# Schematic.net
KiCad netlist of a schematic drawn in EAGLE
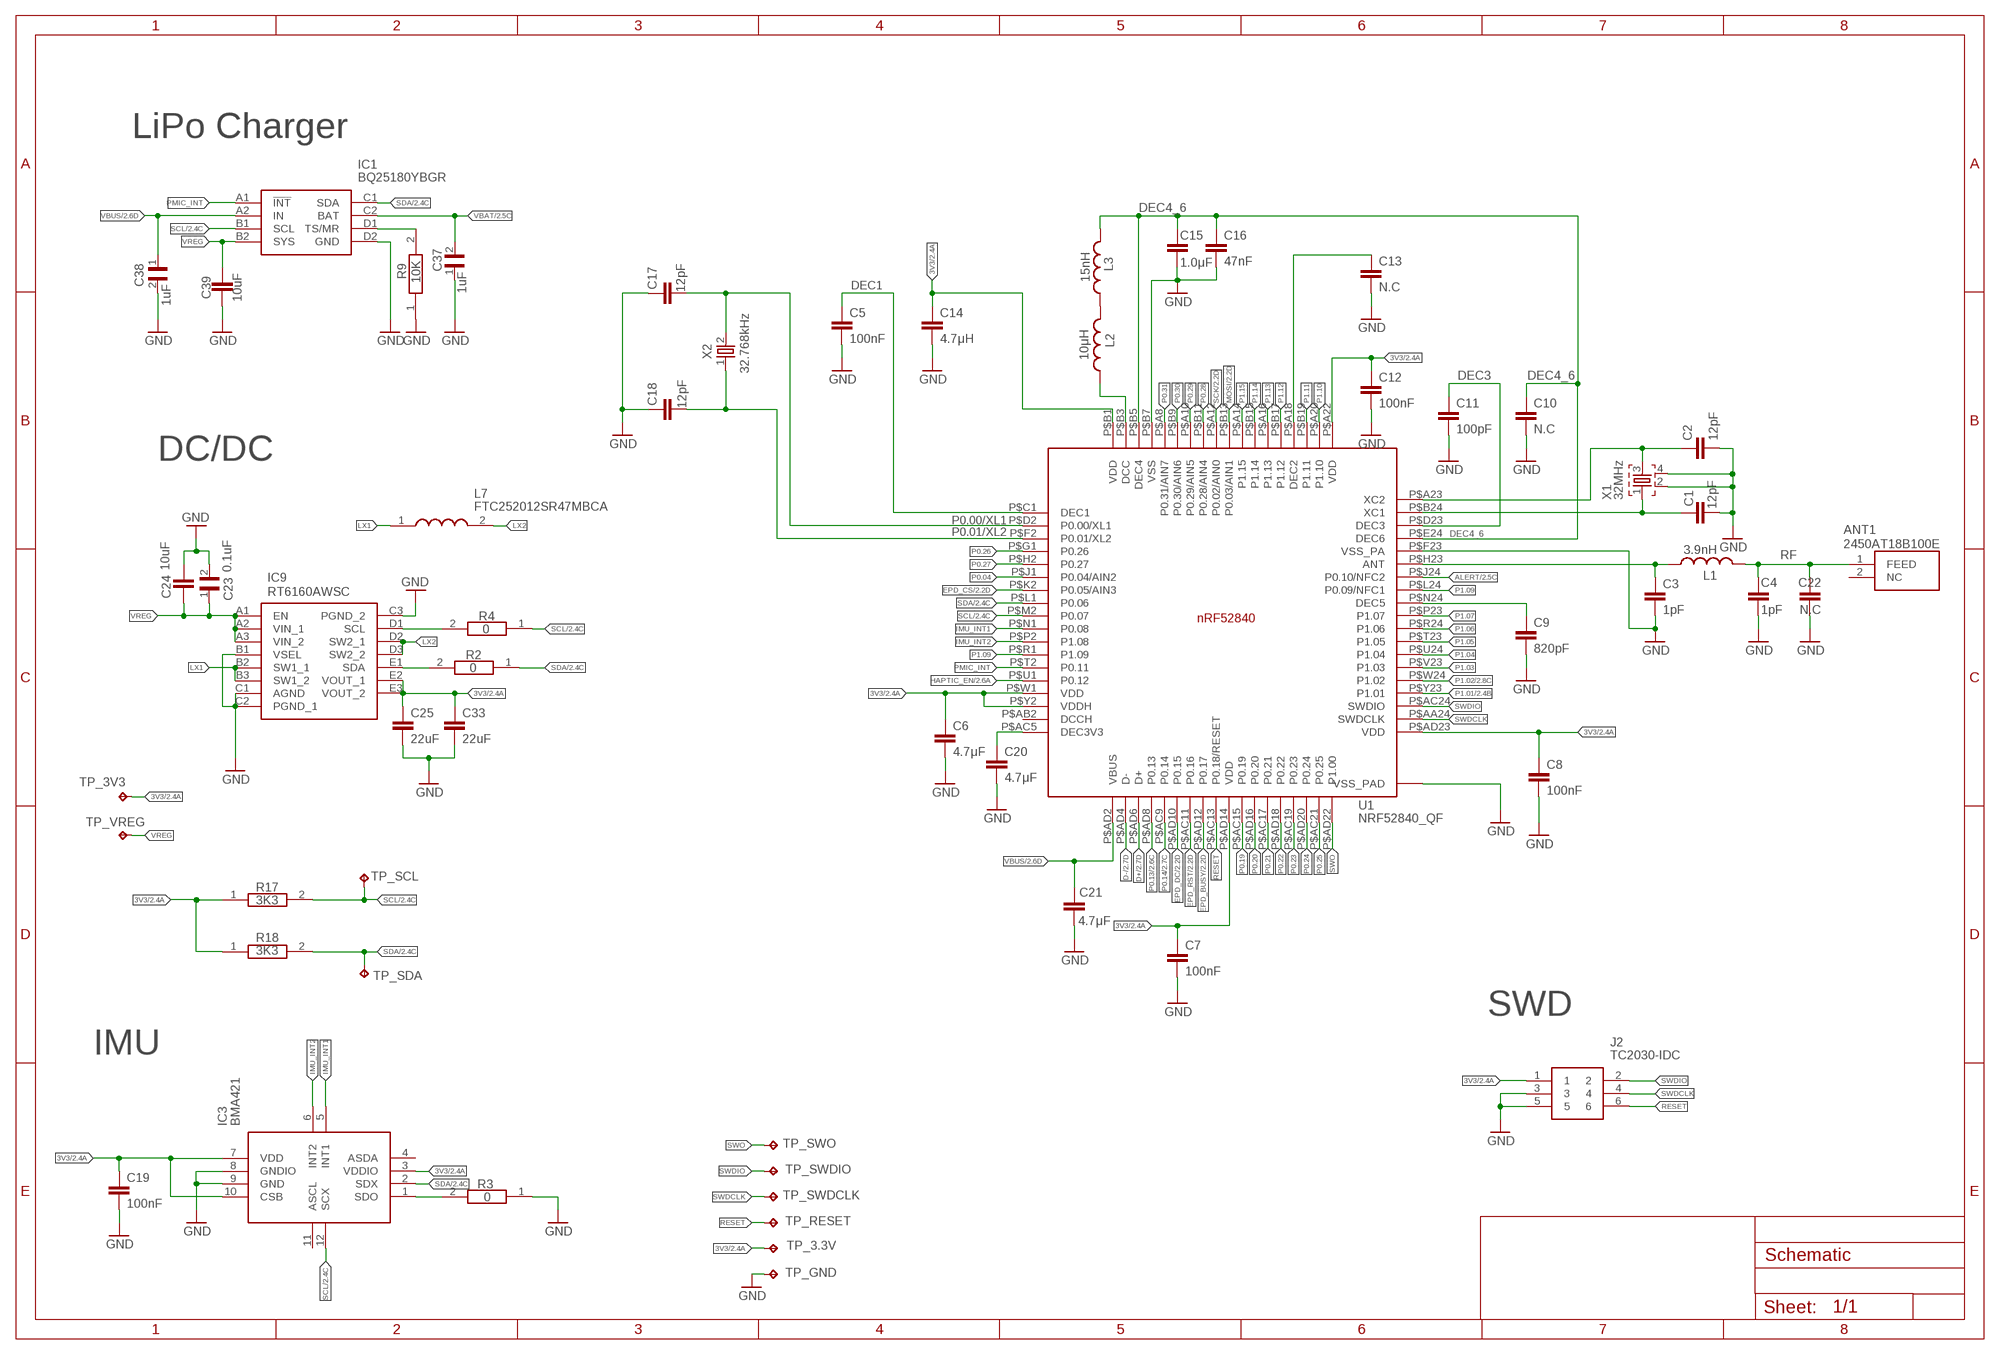
[diagram p0: schematic, sheet 1, part 1 of 2]
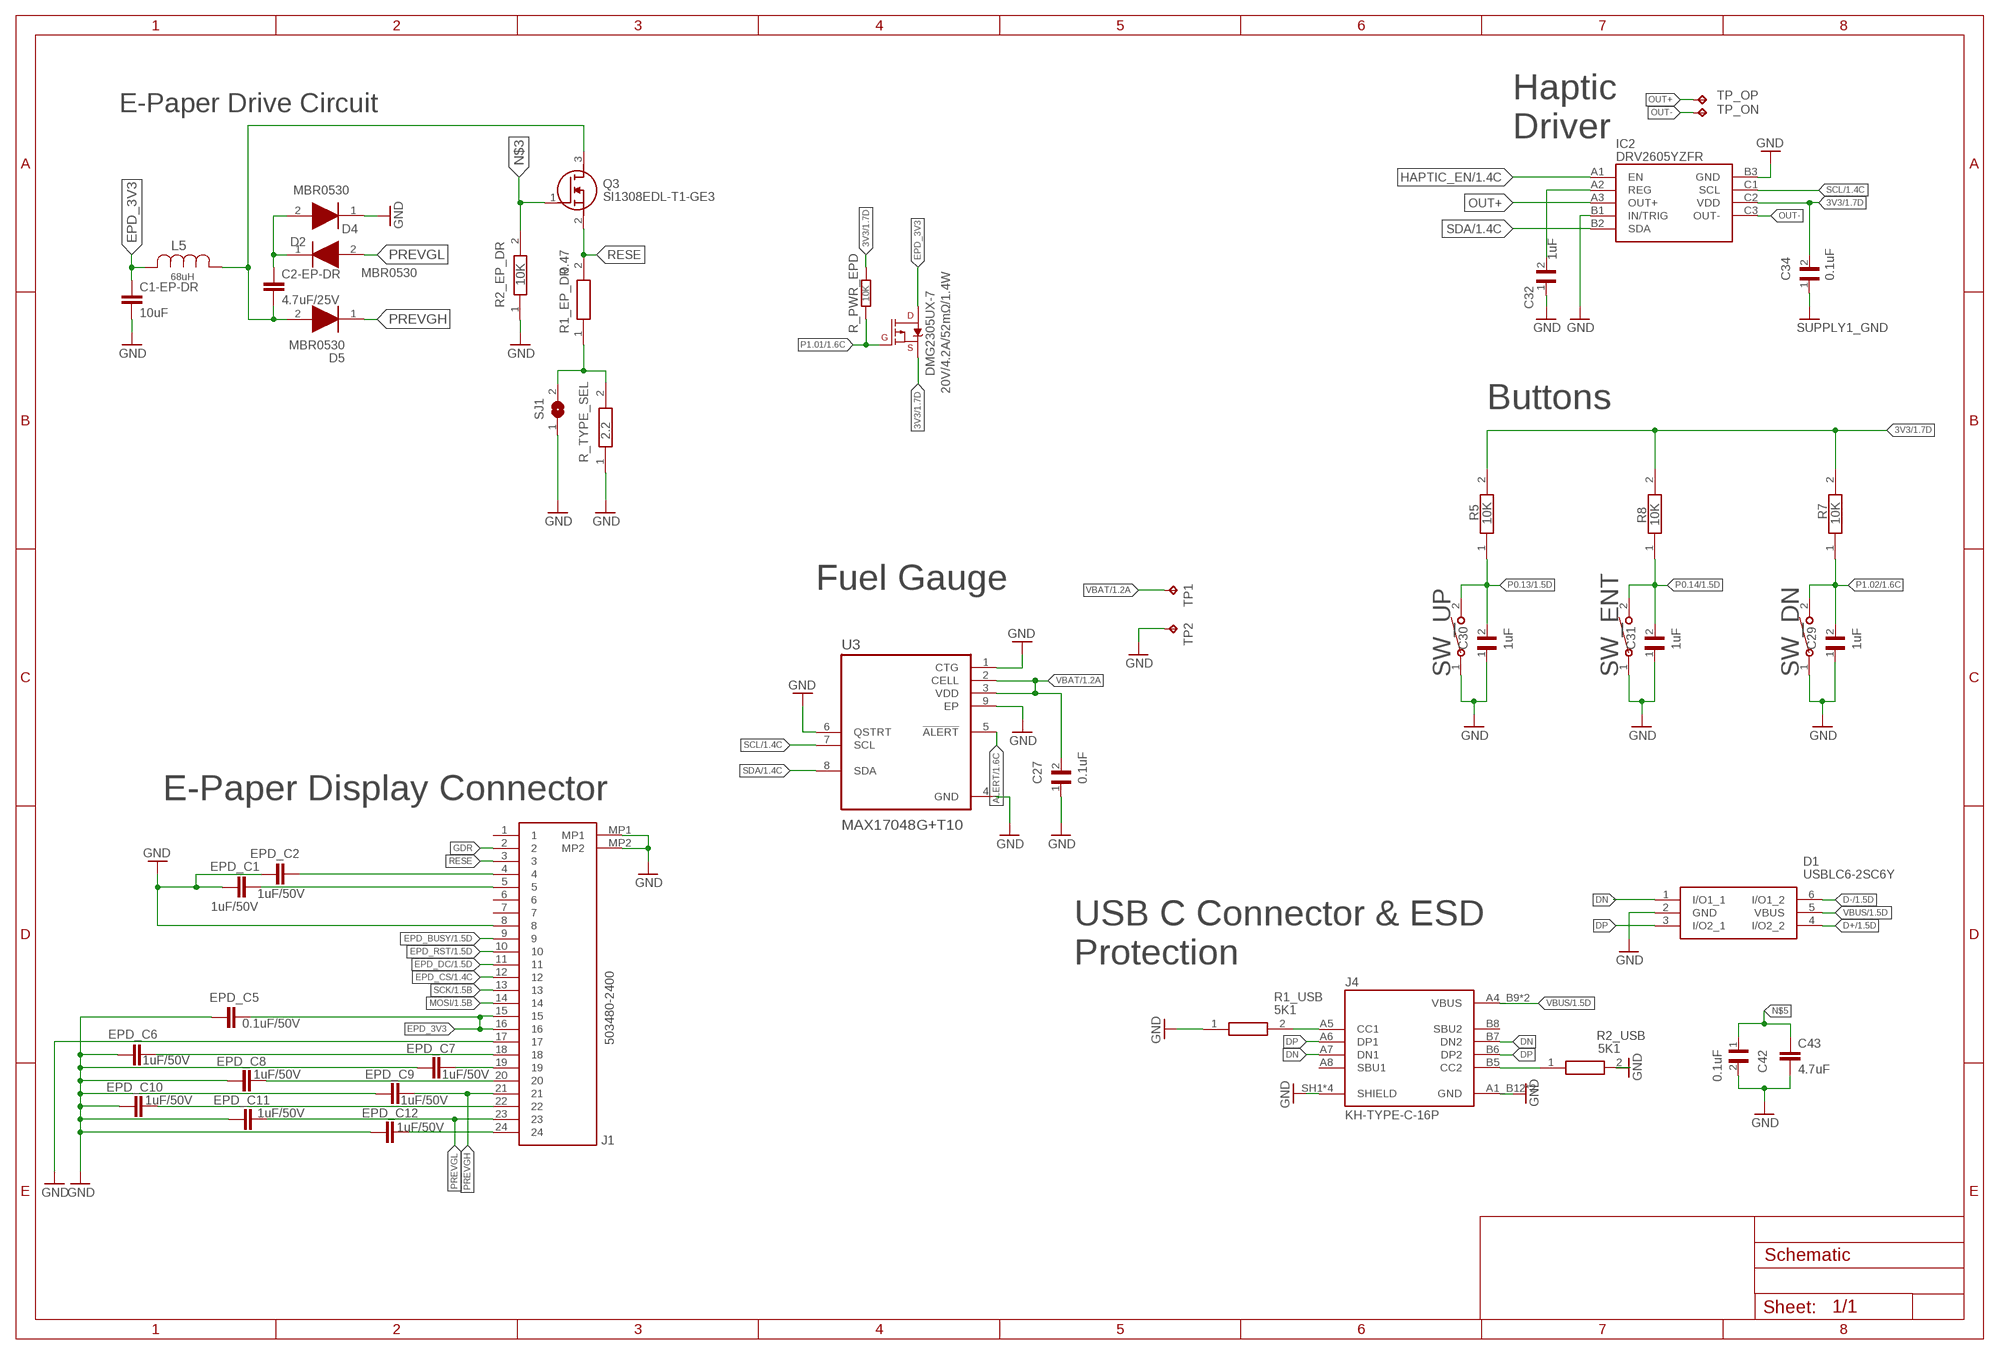
[diagram p1: schematic, sheet 1, part 2 of 2]

(export (version "E")
  (design (tool "Eeschema 10.0.6"))
  (components
    (comp (ref "ANT1")
      (value "2450AT18B100E")
      (footprint "eagle-import:2450AT18B100E_ANTC3216X140N")
      (fields (field (name "MOUSER_PART_NUMBER") "609-2450AT18B100E"))
      (libsource (lib "eagle-import") (part "2450AT18B100E_2450AT18B100E"))
    )
    (comp (ref "C1")
      (value "12pF")
      (footprint "eagle-import:NORDIC_NRF_3_RESC0201_L")
      (libsource (lib "eagle-import") (part "NORDIC_NRF_3_CAPACITOR_0201_L"))
    )
    (comp (ref "C1-EP-DR")
      (value "10uF")
      (footprint "eagle-import:NORDIC_NRF_3_RESC0201_L")
      (libsource (lib "eagle-import") (part "NORDIC_NRF_3_CAPACITOR_0201_L"))
    )
    (comp (ref "C2")
      (value "12pF")
      (footprint "eagle-import:NORDIC_NRF_3_RESC0201_L")
      (libsource (lib "eagle-import") (part "NORDIC_NRF_3_CAPACITOR_0201_L"))
    )
    (comp (ref "C2-EP-DR")
      (value "4.7uF/25V")
      (footprint "eagle-import:NORDIC_NRF_3_RESC0201_L")
      (libsource (lib "eagle-import") (part "NORDIC_NRF_3_CAPACITOR_0201_L"))
    )
    (comp (ref "C3")
      (value "1pF")
      (footprint "eagle-import:NORDIC_NRF_3_RESC0201_L")
      (libsource (lib "eagle-import") (part "NORDIC_NRF_3_CAPACITOR_0201_L"))
    )
    (comp (ref "C4")
      (value "1pF")
      (footprint "eagle-import:NORDIC_NRF_3_RESC0201_L")
      (libsource (lib "eagle-import") (part "NORDIC_NRF_3_CAPACITOR_0201_L"))
    )
    (comp (ref "C5")
      (value "100nF")
      (footprint "eagle-import:NORDIC_NRF_3_RESC0201_L")
      (libsource (lib "eagle-import") (part "NORDIC_NRF_3_CAPACITOR_0201_L"))
    )
    (comp (ref "C6")
      (value "4.7μF")
      (footprint "eagle-import:NORDIC_NRF_3_RESC0201_L")
      (libsource (lib "eagle-import") (part "NORDIC_NRF_3_CAPACITOR_0201_L"))
    )
    (comp (ref "C7")
      (value "100nF")
      (footprint "eagle-import:NORDIC_NRF_3_RESC0201_L")
      (libsource (lib "eagle-import") (part "NORDIC_NRF_3_CAPACITOR_0201_L"))
    )
    (comp (ref "C8")
      (value "100nF")
      (footprint "eagle-import:NORDIC_NRF_3_RESC0201_L")
      (libsource (lib "eagle-import") (part "NORDIC_NRF_3_CAPACITOR_0201_L"))
    )
    (comp (ref "C9")
      (value "820pF")
      (footprint "eagle-import:NORDIC_NRF_3_RESC0201_L")
      (libsource (lib "eagle-import") (part "NORDIC_NRF_3_CAPACITOR_0201_L"))
    )
    (comp (ref "C10")
      (value "N.C")
      (footprint "eagle-import:NORDIC_NRF_3_RESC0201_L")
      (libsource (lib "eagle-import") (part "NORDIC_NRF_3_CAPACITOR_0201_L"))
    )
    (comp (ref "C11")
      (value "100pF")
      (footprint "eagle-import:NORDIC_NRF_3_RESC0201_L")
      (libsource (lib "eagle-import") (part "NORDIC_NRF_3_CAPACITOR_0201_L"))
    )
    (comp (ref "C12")
      (value "100nF")
      (footprint "eagle-import:NORDIC_NRF_3_RESC0201_L")
      (libsource (lib "eagle-import") (part "NORDIC_NRF_3_CAPACITOR_0201_L"))
    )
    (comp (ref "C13")
      (value "N.C")
      (footprint "eagle-import:NORDIC_NRF_3_RESC0201_L")
      (libsource (lib "eagle-import") (part "NORDIC_NRF_3_CAPACITOR_0201_L"))
    )
    (comp (ref "C14")
      (value "4.7μH")
      (footprint "eagle-import:NORDIC_NRF_3_RESC0201_L")
      (libsource (lib "eagle-import") (part "NORDIC_NRF_3_CAPACITOR_0201_L"))
    )
    (comp (ref "C15")
      (value "1.0μF")
      (footprint "eagle-import:NORDIC_NRF_3_RESC0201_L")
      (libsource (lib "eagle-import") (part "NORDIC_NRF_3_CAPACITOR_0201_L"))
    )
    (comp (ref "C16")
      (value "47nF")
      (footprint "eagle-import:NORDIC_NRF_3_RESC0201_L")
      (libsource (lib "eagle-import") (part "NORDIC_NRF_3_CAPACITOR_0201_L"))
    )
    (comp (ref "C17")
      (value "12pF")
      (footprint "eagle-import:NORDIC_NRF_3_RESC0201_L")
      (libsource (lib "eagle-import") (part "NORDIC_NRF_3_CAPACITOR_0201_L"))
    )
    (comp (ref "C18")
      (value "12pF")
      (footprint "eagle-import:NORDIC_NRF_3_RESC0201_L")
      (libsource (lib "eagle-import") (part "NORDIC_NRF_3_CAPACITOR_0201_L"))
    )
    (comp (ref "C19")
      (value "100nF")
      (footprint "eagle-import:NORDIC_NRF_3_RESC0201_L")
      (libsource (lib "eagle-import") (part "NORDIC_NRF_3_CAPACITOR_0201_L"))
    )
    (comp (ref "C20")
      (value "4.7μF")
      (footprint "eagle-import:NORDIC_NRF_3_RESC0201_L")
      (libsource (lib "eagle-import") (part "NORDIC_NRF_3_CAPACITOR_0201_L"))
    )
    (comp (ref "C21")
      (value "4.7μF")
      (footprint "eagle-import:NORDIC_NRF_3_RESC0201_L")
      (libsource (lib "eagle-import") (part "NORDIC_NRF_3_CAPACITOR_0201_L"))
    )
    (comp (ref "C22")
      (value "N.C")
      (footprint "eagle-import:NORDIC_NRF_3_RESC0201_L")
      (libsource (lib "eagle-import") (part "NORDIC_NRF_3_CAPACITOR_0201_L"))
    )
    (comp (ref "C23")
      (value "0.1uF")
      (footprint "eagle-import:GRM011R60J152KE01L_2_CAPC0201X13N")
      (fields (field (name "MF") "Murata") (field (name "MP") "GRM011R60J152KE01L"))
      (libsource (lib "eagle-import") (part "GRM011R60J152KE01L_2_GRM011R60J152KE01L"))
    )
    (comp (ref "C24")
      (value "10uF")
      (footprint "eagle-import:NORDIC_NRF_3_RESC0201_L")
      (libsource (lib "eagle-import") (part "NORDIC_NRF_3_CAPACITOR_0201_L"))
    )
    (comp (ref "C25")
      (value "22uF")
      (footprint "eagle-import:NORDIC_NRF_3_RESC0201_L")
      (libsource (lib "eagle-import") (part "NORDIC_NRF_3_CAPACITOR_0201_L"))
    )
    (comp (ref "C27")
      (value "0.1uF")
      (footprint "eagle-import:GRM011R60J152KE01L_2_CAPC0201X13N")
      (fields (field (name "MF") "Murata") (field (name "MP") "GRM011R60J152KE01L"))
      (libsource (lib "eagle-import") (part "GRM011R60J152KE01L_2_GRM011R60J152KE01L"))
    )
    (comp (ref "C29")
      (value "1uF")
      (footprint "eagle-import:GRM011R60J152KE01L_2_CAPC0201X13N")
      (fields (field (name "MF") "Murata") (field (name "MP") "GRM011R60J152KE01L"))
      (libsource (lib "eagle-import") (part "GRM011R60J152KE01L_2_GRM011R60J152KE01L"))
    )
    (comp (ref "C30")
      (value "1uF")
      (footprint "eagle-import:GRM011R60J152KE01L_2_CAPC0201X13N")
      (fields (field (name "MF") "Murata") (field (name "MP") "GRM011R60J152KE01L"))
      (libsource (lib "eagle-import") (part "GRM011R60J152KE01L_2_GRM011R60J152KE01L"))
    )
    (comp (ref "C31")
      (value "1uF")
      (footprint "eagle-import:GRM011R60J152KE01L_2_CAPC0201X13N")
      (fields (field (name "MF") "Murata") (field (name "MP") "GRM011R60J152KE01L"))
      (libsource (lib "eagle-import") (part "GRM011R60J152KE01L_2_GRM011R60J152KE01L"))
    )
    (comp (ref "C32")
      (value "1uF")
      (footprint "eagle-import:GRM011R60J152KE01L_2_CAPC0201X13N")
      (fields (field (name "MF") "Murata") (field (name "MP") "GRM011R60J152KE01L"))
      (libsource (lib "eagle-import") (part "GRM011R60J152KE01L_2_GRM011R60J152KE01L"))
    )
    (comp (ref "C33")
      (value "22uF")
      (footprint "eagle-import:NORDIC_NRF_3_RESC0201_L")
      (libsource (lib "eagle-import") (part "NORDIC_NRF_3_CAPACITOR_0201_L"))
    )
    (comp (ref "C34")
      (value "0.1uF")
      (footprint "eagle-import:GRM011R60J152KE01L_2_CAPC0201X13N")
      (fields (field (name "MF") "Murata") (field (name "MP") "GRM011R60J152KE01L"))
      (libsource (lib "eagle-import") (part "GRM011R60J152KE01L_2_GRM011R60J152KE01L"))
    )
    (comp (ref "C37")
      (value "1uF")
      (footprint "eagle-import:GRM011R60J152KE01L_2_CAPC0201X13N")
      (fields (field (name "MF") "Murata") (field (name "MP") "GRM011R60J152KE01L"))
      (libsource (lib "eagle-import") (part "GRM011R60J152KE01L_2_GRM011R60J152KE01L"))
    )
    (comp (ref "C38")
      (value "1uF")
      (footprint "eagle-import:GRM011R60J152KE01L_2_CAPC0201X13N")
      (fields (field (name "MF") "Murata") (field (name "MP") "GRM011R60J152KE01L"))
      (libsource (lib "eagle-import") (part "GRM011R60J152KE01L_2_GRM011R60J152KE01L"))
    )
    (comp (ref "C39")
      (value "10uF")
      (footprint "eagle-import:NORDIC_NRF_3_RESC0201_L")
      (libsource (lib "eagle-import") (part "NORDIC_NRF_3_CAPACITOR_0201_L"))
    )
    (comp (ref "C42")
      (value "0.1uF")
      (footprint "eagle-import:GRM011R60J152KE01L_2_CAPC0201X13N")
      (fields (field (name "MF") "Murata") (field (name "MP") "GRM011R60J152KE01L"))
      (libsource (lib "eagle-import") (part "GRM011R60J152KE01L_2_GRM011R60J152KE01L"))
    )
    (comp (ref "C43")
      (value "4.7uF")
      (footprint "eagle-import:NORDIC_NRF_3_RESC0201_L")
      (libsource (lib "eagle-import") (part "NORDIC_NRF_3_CAPACITOR_0201_L"))
    )
    (comp (ref "D1")
      (value "USBLC6-2SC6Y")
      (footprint "eagle-import:ESP32_C6_LIBRARY_3_SOT95P280X145-6N")
      (fields (field (name "MF") "STMicroelectronics"))
      (libsource (lib "eagle-import") (part "ESP32_C6_LIBRARY_3_USBLC6-2SC6Y"))
    )
    (comp (ref "D2")
      (value "MBR0530")
      (footprint "eagle-import:ESP32_C6_LIBRARY_5_SOD3716X135N")
      (fields (field (name "MF") "ON Semiconductor"))
      (libsource (lib "eagle-import") (part "ESP32_C6_LIBRARY_5_MBR0530"))
    )
    (comp (ref "D4")
      (value "MBR0530")
      (footprint "eagle-import:ESP32_C6_LIBRARY_5_SOD3716X135N")
      (fields (field (name "MF") "ON Semiconductor"))
      (libsource (lib "eagle-import") (part "ESP32_C6_LIBRARY_5_MBR0530"))
    )
    (comp (ref "D5")
      (value "MBR0530")
      (footprint "eagle-import:ESP32_C6_LIBRARY_5_SOD3716X135N")
      (fields (field (name "MF") "ON Semiconductor"))
      (libsource (lib "eagle-import") (part "ESP32_C6_LIBRARY_5_MBR0530"))
    )
    (comp (ref "DMG2305UX-7")
      (value "20V/4.2A/52mΩ/1.4W")
      (footprint "eagle-import:ESP32_C6_LIBRARY_4_ESP32_C6_LIBRARY_4_ESP32_C6_LIBRARY_4_ESP32_C6_LIBRARY_4_ESP32_WROVER_SPARKFUN-DISCRETESEMI_SOT23-3")
      (libsource (lib "eagle-import") (part "ESP32_C6_LIBRARY_4_ESP32_WROVER_SPARKFUN-DISCRETESEMI_MOSFET_PCH-DMG2305UX-7"))
    )
    (comp (ref "EPD_C1")
      (value "1uF/50V")
      (footprint "eagle-import:NORDIC_NRF_3_RESC0201_L")
      (libsource (lib "eagle-import") (part "NORDIC_NRF_3_CAPACITOR_0201_L"))
    )
    (comp (ref "EPD_C2")
      (value "1uF/50V")
      (footprint "eagle-import:NORDIC_NRF_3_RESC0201_L")
      (libsource (lib "eagle-import") (part "NORDIC_NRF_3_CAPACITOR_0201_L"))
    )
    (comp (ref "EPD_C5")
      (value "0.1uF/50V")
      (footprint "eagle-import:NORDIC_NRF_3_RESC0201_L")
      (libsource (lib "eagle-import") (part "NORDIC_NRF_3_CAPACITOR_0201_L"))
    )
    (comp (ref "EPD_C6")
      (value "1uF/50V")
      (footprint "eagle-import:NORDIC_NRF_3_RESC0201_L")
      (libsource (lib "eagle-import") (part "NORDIC_NRF_3_CAPACITOR_0201_L"))
    )
    (comp (ref "EPD_C7")
      (value "1uF/50V")
      (footprint "eagle-import:NORDIC_NRF_3_RESC0201_L")
      (libsource (lib "eagle-import") (part "NORDIC_NRF_3_CAPACITOR_0201_L"))
    )
    (comp (ref "EPD_C8")
      (value "1uF/50V")
      (footprint "eagle-import:NORDIC_NRF_3_RESC0201_L")
      (libsource (lib "eagle-import") (part "NORDIC_NRF_3_CAPACITOR_0201_L"))
    )
    (comp (ref "EPD_C9")
      (value "1uF/50V")
      (footprint "eagle-import:NORDIC_NRF_3_RESC0201_L")
      (libsource (lib "eagle-import") (part "NORDIC_NRF_3_CAPACITOR_0201_L"))
    )
    (comp (ref "EPD_C10")
      (value "1uF/50V")
      (footprint "eagle-import:NORDIC_NRF_3_RESC0201_L")
      (libsource (lib "eagle-import") (part "NORDIC_NRF_3_CAPACITOR_0201_L"))
    )
    (comp (ref "EPD_C11")
      (value "1uF/50V")
      (footprint "eagle-import:NORDIC_NRF_3_RESC0201_L")
      (libsource (lib "eagle-import") (part "NORDIC_NRF_3_CAPACITOR_0201_L"))
    )
    (comp (ref "EPD_C12")
      (value "1uF/50V")
      (footprint "eagle-import:NORDIC_NRF_3_RESC0201_L")
      (libsource (lib "eagle-import") (part "NORDIC_NRF_3_CAPACITOR_0201_L"))
    )
    (comp (ref "IC1")
      (value "BQ25180YBGR")
      (footprint "eagle-import:BQ25180YBGR_BGA8C40P2X4_100X155X50")
      (fields (field (name "MOUSER_PART_NUMBER") "595-BQ25180YBGR"))
      (libsource (lib "eagle-import") (part "BQ25180YBGR_BQ25180YBGR"))
    )
    (comp (ref "IC2")
      (value "DRV2605YZFR")
      (footprint "eagle-import:DRV2605YZFR_BGA9C50P3X3_144X144X62")
      (libsource (lib "eagle-import") (part "DRV2605YZFR_DRV2605YZFR"))
    )
    (comp (ref "IC3")
      (value "BMA421")
      (footprint "eagle-import:BMA423_BMA423")
      (fields
        (field (name "MANUFACTURER_PART_NUMBER") "BMA423")
        (field (name "MOUSER_PART_NUMBER") "262-BMA423")
      )
      (libsource (lib "eagle-import") (part "BMA423_BMA423"))
    )
    (comp (ref "IC9")
      (value "RT6160AWSC")
      (footprint "eagle-import:RT6160AWSC_BGA15C40P3X5_140X230X60")
      (fields (field (name "MOUSER_PART_NUMBER") "835-RT6160AWSC"))
      (libsource (lib "eagle-import") (part "RT6160AWSC_RT6160AWSC"))
    )
    (comp (ref "J1")
      (value "503480-2400")
      (footprint "eagle-import:503480-2400_5034802400")
      (fields (field (name "MOUSER_PART_NUMBER") "538-503480-2400"))
      (libsource (lib "eagle-import") (part "503480-2400_503480-2400"))
    )
    (comp (ref "J2")
      (value "TC2030-IDC")
      (footprint "eagle-import:TC2030-IDC_TC2030IDC")
      (libsource (lib "eagle-import") (part "TC2030-IDC_TC2030-IDC"))
    )
    (comp (ref "J4")
      (value "KH-TYPE-C-16P")
      (footprint "eagle-import:KH-TYPE-C-16P_KINGHELM_KH-TYPE-C-16P")
      (fields (field (name "MF") "kinghelm"))
      (libsource (lib "eagle-import") (part "KH-TYPE-C-16P_KH-TYPE-C-16P"))
    )
    (comp (ref "L1")
      (value "3.9nH")
      (footprint "eagle-import:NORDIC_NRF_2_RESC0402_L")
      (libsource (lib "eagle-import") (part "NORDIC_NRF_2_INDUCTOR_0402_L"))
    )
    (comp (ref "L2")
      (value "10μH")
      (footprint "eagle-import:NORDIC_NRF_2_RESC0402_L")
      (libsource (lib "eagle-import") (part "NORDIC_NRF_2_INDUCTOR_0402_L"))
    )
    (comp (ref "L3")
      (value "15nH")
      (footprint "eagle-import:NORDIC_NRF_2_RESC0402_L")
      (libsource (lib "eagle-import") (part "NORDIC_NRF_2_INDUCTOR_0402_L"))
    )
    (comp (ref "L5")
      (value "68uH")
      (footprint "eagle-import:ESP32_C6_LIBRARY_2_IND_4828-WE-TPC_WRE")
      (fields
        (field (name "MANUFACTURER_PART_NUMBER") "744043680")
        (field (name "COPYRIGHT") "Copyright (C) 2024 Ultra Librarian. All rights reserved.")
      )
      (libsource (lib "eagle-import") (part "ESP32_C6_LIBRARY_2_744043680IND_4828-WE-TPC_WRE"))
    )
    (comp (ref "L7")
      (value "FTC252012SR47MBCA")
      (footprint "eagle-import:MLP2016SR47MT0S1_INDC2016X100N")
      (libsource (lib "eagle-import") (part "MLP2016SR47MT0S1_FTC252012SR47MBCA"))
    )
    (comp (ref "Q3")
      (value "SI1308EDL-T1-GE3")
      (footprint "eagle-import:ESP32_C6_LIBRARY_6_SOT65P210X110-3N")
      (fields (field (name "MF") "Vishay Siliconix"))
      (libsource (lib "eagle-import") (part "ESP32_C6_LIBRARY_6_SI1308EDL-T1-GE3"))
    )
    (comp (ref "R1_EP_DR")
      (value "0.47")
      (footprint "eagle-import:CPF0201D7K68C1_0201")
      (libsource (lib "eagle-import") (part "CPF0201D7K68C1_CPF0201D7K68C1"))
    )
    (comp (ref "R1_USB")
      (value "5K1")
      (footprint "eagle-import:CPF0201D7K68C1_0201")
      (libsource (lib "eagle-import") (part "CPF0201D7K68C1_CPF0201D7K68C1"))
    )
    (comp (ref "R2")
      (value "0")
      (footprint "eagle-import:CPF0201D7K68C1_0201")
      (libsource (lib "eagle-import") (part "CPF0201D7K68C1_CPF0201D7K68C1"))
    )
    (comp (ref "R2_EP_DR")
      (value "10K")
      (footprint "eagle-import:CPF0201D7K68C1_0201")
      (libsource (lib "eagle-import") (part "CPF0201D7K68C1_CPF0201D7K68C1"))
    )
    (comp (ref "R2_USB")
      (value "5K1")
      (footprint "eagle-import:CPF0201D7K68C1_0201")
      (libsource (lib "eagle-import") (part "CPF0201D7K68C1_CPF0201D7K68C1"))
    )
    (comp (ref "R3")
      (value "0")
      (footprint "eagle-import:CPF0201D7K68C1_0201")
      (libsource (lib "eagle-import") (part "CPF0201D7K68C1_CPF0201D7K68C1"))
    )
    (comp (ref "R4")
      (value "0")
      (footprint "eagle-import:CPF0201D7K68C1_0201")
      (libsource (lib "eagle-import") (part "CPF0201D7K68C1_CPF0201D7K68C1"))
    )
    (comp (ref "R5")
      (value "10K")
      (footprint "eagle-import:CPF0201D7K68C1_0201")
      (libsource (lib "eagle-import") (part "CPF0201D7K68C1_CPF0201D7K68C1"))
    )
    (comp (ref "R7")
      (value "10K")
      (footprint "eagle-import:CPF0201D7K68C1_0201")
      (libsource (lib "eagle-import") (part "CPF0201D7K68C1_CPF0201D7K68C1"))
    )
    (comp (ref "R8")
      (value "10K")
      (footprint "eagle-import:CPF0201D7K68C1_0201")
      (libsource (lib "eagle-import") (part "CPF0201D7K68C1_CPF0201D7K68C1"))
    )
    (comp (ref "R9")
      (value "10K")
      (footprint "eagle-import:CPF0201D7K68C1_0201")
      (libsource (lib "eagle-import") (part "CPF0201D7K68C1_CPF0201D7K68C1"))
    )
    (comp (ref "R17")
      (value "3K3")
      (footprint "eagle-import:CPF0201D7K68C1_0201")
      (libsource (lib "eagle-import") (part "CPF0201D7K68C1_CPF0201D7K68C1"))
    )
    (comp (ref "R18")
      (value "3K3")
      (footprint "eagle-import:CPF0201D7K68C1_0201")
      (libsource (lib "eagle-import") (part "CPF0201D7K68C1_CPF0201D7K68C1"))
    )
    (comp (ref "R_PWR_EPD")
      (value "10K")
      (footprint "eagle-import:RESC1005X40")
      (libsource (lib "eagle-import") (part "RESISTOR_CHIP-0402(1005-METRIC)_"))
    )
    (comp (ref "R_TYPE_SEL")
      (value "2.2")
      (footprint "eagle-import:CPF0201D7K68C1_0201")
      (libsource (lib "eagle-import") (part "CPF0201D7K68C1_CPF0201D7K68C1"))
    )
    (comp (ref "SJ1")
      (value "ESP32_C6_LIBRARY_7_JUMPER_SJ")
      (footprint "eagle-import:ESP32_C6_LIBRARY_7_JUMPER_SJ")
      (libsource (lib "eagle-import") (part "ESP32_C6_LIBRARY_7_JUMPER_SJ"))
    )
    (comp (ref "SW_DN")
      (value "2025-10-22_07-23-44_LIBRARY_EVP-AKE31ASW_EVP-AKE31A_PAN")
      (footprint "eagle-import:2025-10-22_07-23-44_LIBRARY_SW_EVP-AKE31A_PAN")
      (fields
        (field (name "MANUFACTURER_PART_NUMBER") "EVP-AKE31A")
        (field (name "COPYRIGHT") "Copyright (C) 2025 Ultra Librarian. All rights reserved.")
      )
      (libsource (lib "eagle-import") (part "2025-10-22_07-23-44_LIBRARY_EVP-AKE31ASW_EVP-AKE31A_PAN"))
    )
    (comp (ref "SW_ENT")
      (value "2025-10-22_07-23-44_LIBRARY_EVP-AKE31ASW_EVP-AKE31A_PAN")
      (footprint "eagle-import:2025-10-22_07-23-44_LIBRARY_SW_EVP-AKE31A_PAN")
      (fields
        (field (name "MANUFACTURER_PART_NUMBER") "EVP-AKE31A")
        (field (name "COPYRIGHT") "Copyright (C) 2025 Ultra Librarian. All rights reserved.")
      )
      (libsource (lib "eagle-import") (part "2025-10-22_07-23-44_LIBRARY_EVP-AKE31ASW_EVP-AKE31A_PAN"))
    )
    (comp (ref "SW_UP")
      (value "2025-10-22_07-23-44_LIBRARY_EVP-AKE31ASW_EVP-AKE31A_PAN")
      (footprint "eagle-import:2025-10-22_07-23-44_LIBRARY_SW_EVP-AKE31A_PAN")
      (fields
        (field (name "MANUFACTURER_PART_NUMBER") "EVP-AKE31A")
        (field (name "COPYRIGHT") "Copyright (C) 2025 Ultra Librarian. All rights reserved.")
      )
      (libsource (lib "eagle-import") (part "2025-10-22_07-23-44_LIBRARY_EVP-AKE31ASW_EVP-AKE31A_PAN"))
    )
    (comp (ref "TP1")
      (value "HECTOR_WATCH_1_TPTP20R")
      (footprint "eagle-import:HECTOR_WATCH_1_TP20R")
      (libsource (lib "eagle-import") (part "HECTOR_WATCH_1_TPTP20R"))
    )
    (comp (ref "TP2")
      (value "HECTOR_WATCH_1_TPTP20R")
      (footprint "eagle-import:HECTOR_WATCH_1_TP20R")
      (libsource (lib "eagle-import") (part "HECTOR_WATCH_1_TPTP20R"))
    )
    (comp (ref "TP_3.3V")
      (value "HECTOR_WATCH_1_TPTP20R")
      (footprint "eagle-import:HECTOR_WATCH_1_TP20R")
      (libsource (lib "eagle-import") (part "HECTOR_WATCH_1_TPTP20R"))
    )
    (comp (ref "TP_3V3")
      (value "HECTOR_WATCH_1_TPTP20R")
      (footprint "eagle-import:HECTOR_WATCH_1_TP20R")
      (libsource (lib "eagle-import") (part "HECTOR_WATCH_1_TPTP20R"))
    )
    (comp (ref "TP_GND")
      (value "HECTOR_WATCH_1_TPTP20R")
      (footprint "eagle-import:HECTOR_WATCH_1_TP20R")
      (libsource (lib "eagle-import") (part "HECTOR_WATCH_1_TPTP20R"))
    )
    (comp (ref "TP_ON")
      (value "HECTOR_WATCH_1_TPTP20R")
      (footprint "eagle-import:HECTOR_WATCH_1_TP20R")
      (libsource (lib "eagle-import") (part "HECTOR_WATCH_1_TPTP20R"))
    )
    (comp (ref "TP_OP")
      (value "TP_OP")
      (footprint "eagle-import:HECTOR_WATCH_1_TP20R")
      (libsource (lib "eagle-import") (part "HECTOR_WATCH_1_TPTP20R"))
    )
    (comp (ref "TP_RESET")
      (value "HECTOR_WATCH_1_TPTP20R")
      (footprint "eagle-import:HECTOR_WATCH_1_TP20R")
      (libsource (lib "eagle-import") (part "HECTOR_WATCH_1_TPTP20R"))
    )
    (comp (ref "TP_SCL")
      (value "HECTOR_WATCH_1_TPTP20R")
      (footprint "eagle-import:HECTOR_WATCH_1_TP20R")
      (libsource (lib "eagle-import") (part "HECTOR_WATCH_1_TPTP20R"))
    )
    (comp (ref "TP_SDA")
      (value "HECTOR_WATCH_1_TPTP20R")
      (footprint "eagle-import:HECTOR_WATCH_1_TP20R")
      (libsource (lib "eagle-import") (part "HECTOR_WATCH_1_TPTP20R"))
    )
    (comp (ref "TP_SWDCLK")
      (value "HECTOR_WATCH_1_TPTP20R")
      (footprint "eagle-import:HECTOR_WATCH_1_TP20R")
      (libsource (lib "eagle-import") (part "HECTOR_WATCH_1_TPTP20R"))
    )
    (comp (ref "TP_SWDIO")
      (value "HECTOR_WATCH_1_TPTP20R")
      (footprint "eagle-import:HECTOR_WATCH_1_TP20R")
      (libsource (lib "eagle-import") (part "HECTOR_WATCH_1_TPTP20R"))
    )
    (comp (ref "TP_SWO")
      (value "HECTOR_WATCH_1_TPTP20R")
      (footprint "eagle-import:HECTOR_WATCH_1_TP20R")
      (libsource (lib "eagle-import") (part "HECTOR_WATCH_1_TPTP20R"))
    )
    (comp (ref "TP_VREG")
      (value "HECTOR_WATCH_1_TPTP20R")
      (footprint "eagle-import:HECTOR_WATCH_1_TP20R")
      (libsource (lib "eagle-import") (part "HECTOR_WATCH_1_TPTP20R"))
    )
    (comp (ref "U1")
      (value "NRF52840_QF")
      (footprint "eagle-import:NORDIC_NRF_4_AQFN50P700X700X85_HS-74N")
      (libsource (lib "eagle-import") (part "NORDIC_NRF_4_NRF52840_QF"))
    )
    (comp (ref "U3")
      (value "MAX17048G+T10")
      (footprint "eagle-import:ESP32_C6_LIBRARY_SON50P200X200X80-9N")
      (fields (field (name "MF") "Analog Devices"))
      (libsource (lib "eagle-import") (part "ESP32_C6_LIBRARY_MAX17048G+T10"))
    )
    (comp (ref "X1")
      (value "32MHz")
      (footprint "eagle-import:NORDIC_NRF_BT-XTAL_2016_N")
      (libsource (lib "eagle-import") (part "NORDIC_NRF_XTAL_32MHZ"))
    )
    (comp (ref "X2")
      (value "32.768kHz")
      (footprint "eagle-import:NORDIC_NRF_1_XTAL_3215_N")
      (libsource (lib "eagle-import") (part "NORDIC_NRF_1_XTAL_32KHZ"))
    )
  )
  (nets
    (net (code "1") (name "/DEC1") (class "Default")
      (node (ref "C5") (pin "1") (pinfunction "1_1") (pintype "passive"))
      (node (ref "U1") (pin "P$C1") (pinfunction "DEC1_P$C1") (pintype "power_in"))
    )
    (net (code "2") (name "/DEC3") (class "Default")
      (node (ref "C11") (pin "1") (pinfunction "1_1") (pintype "passive"))
      (node (ref "U1") (pin "P$D23") (pinfunction "DEC3_P$D23") (pintype "bidirectional"))
    )
    (net (code "3") (name "/DEC4_6") (class "Default")
      (node (ref "C10") (pin "1") (pinfunction "1_1") (pintype "passive"))
      (node (ref "C15") (pin "1") (pinfunction "1_1") (pintype "passive"))
      (node (ref "C16") (pin "1") (pinfunction "1_1") (pintype "passive"))
      (node (ref "L3") (pin "2") (pinfunction "2_2") (pintype "passive"))
      (node (ref "U1") (pin "P$B5") (pinfunction "DEC4_P$B5") (pintype "power_in"))
      (node (ref "U1") (pin "P$E24") (pinfunction "DEC6_P$E24") (pintype "bidirectional"))
    )
    (net (code "4") (name "/P0.00{slash}XL1") (class "Default")
      (node (ref "C17") (pin "2") (pinfunction "2_2") (pintype "passive"))
      (node (ref "U1") (pin "P$D2") (pinfunction "P0.00/XL1_P$D2") (pintype "bidirectional"))
      (node (ref "X2") (pin "2") (pinfunction "2_2") (pintype "passive"))
    )
    (net (code "5") (name "/P0.01{slash}XL2") (class "Default")
      (node (ref "C18") (pin "2") (pinfunction "2_2") (pintype "passive"))
      (node (ref "U1") (pin "P$F2") (pinfunction "P0.01/XL2_P$F2") (pintype "bidirectional"))
      (node (ref "X2") (pin "1") (pinfunction "1_1") (pintype "passive"))
    )
    (net (code "6") (name "/RF") (class "Default")
      (node (ref "ANT1") (pin "1") (pinfunction "FEED_1") (pintype "input"))
      (node (ref "C22") (pin "1") (pinfunction "1_1") (pintype "passive"))
      (node (ref "C4") (pin "1") (pinfunction "1_1") (pintype "passive"))
      (node (ref "L1") (pin "2") (pinfunction "2_2") (pintype "passive"))
    )
    (net (code "7") (name "3V3{slash}1.7D") (class "Default")
      (node (ref "C34") (pin "2") (pinfunction "2_2") (pintype "passive"))
      (node (ref "DMG2305UX-7") (pin "2") (pinfunction "S_2") (pintype "bidirectional"))
      (node (ref "IC2") (pin "C2") (pinfunction "VDD_C2") (pintype "bidirectional"))
      (node (ref "R5") (pin "2") (pinfunction "2_2") (pintype "bidirectional"))
      (node (ref "R7") (pin "2") (pinfunction "2_2") (pintype "bidirectional"))
      (node (ref "R8") (pin "2") (pinfunction "2_2") (pintype "bidirectional"))
      (node (ref "R_PWR_EPD") (pin "2") (pinfunction "2_2") (pintype "passive"))
    )
    (net (code "8") (name "3V3{slash}2.4A") (class "Default")
      (node (ref "C12") (pin "1") (pinfunction "1_1") (pintype "passive"))
      (node (ref "C14") (pin "1") (pinfunction "1_1") (pintype "passive"))
      (node (ref "C19") (pin "1") (pinfunction "1_1") (pintype "passive"))
      (node (ref "C25") (pin "1") (pinfunction "1_1") (pintype "passive"))
      (node (ref "C33") (pin "1") (pinfunction "1_1") (pintype "passive"))
      (node (ref "C6") (pin "1") (pinfunction "1_1") (pintype "passive"))
      (node (ref "C7") (pin "1") (pinfunction "1_1") (pintype "passive"))
      (node (ref "C8") (pin "1") (pinfunction "1_1") (pintype "passive"))
      (node (ref "IC3") (pin "10") (pinfunction "CSB_10") (pintype "bidirectional"))
      (node (ref "IC3") (pin "3") (pinfunction "VDDIO_3") (pintype "bidirectional"))
      (node (ref "IC3") (pin "7") (pinfunction "VDD_7") (pintype "bidirectional"))
      (node (ref "IC9") (pin "E2") (pinfunction "VOUT_1_E2") (pintype "bidirectional"))
      (node (ref "IC9") (pin "E3") (pinfunction "VOUT_2_E3") (pintype "bidirectional"))
      (node (ref "J2") (pin "1") (pinfunction "1_1") (pintype "bidirectional"))
      (node (ref "R17") (pin "1") (pinfunction "1_1") (pintype "bidirectional"))
      (node (ref "R18") (pin "1") (pinfunction "1_1") (pintype "bidirectional"))
      (node (ref "TP_3.3V") (pin "TP") (pinfunction "TP_TP") (pintype "input"))
      (node (ref "TP_3V3") (pin "TP") (pinfunction "TP_TP") (pintype "input"))
      (node (ref "U1") (pin "P$A22") (pinfunction "VDD_P$A22") (pintype "power_in"))
      (node (ref "U1") (pin "P$AD14") (pinfunction "VDD_P$AD14") (pintype "power_in"))
      (node (ref "U1") (pin "P$AD23") (pinfunction "VDD_P$AD23") (pintype "power_in"))
      (node (ref "U1") (pin "P$B1") (pinfunction "VDD_P$B1") (pintype "power_in"))
      (node (ref "U1") (pin "P$W1") (pinfunction "VDD_P$W1") (pintype "power_in"))
      (node (ref "U1") (pin "P$Y2") (pinfunction "VDDH_P$Y2") (pintype "power_in"))
    )
    (net (code "9") (name "ALERT{slash}1.6C") (class "Default")
      (node (ref "U3") (pin "5") (pinfunction "~{ALERT}_5") (pintype "output"))
    )
    (net (code "10") (name "ALERT{slash}2.5C") (class "Default")
      (node (ref "U1") (pin "P$J24") (pinfunction "P0.10/NFC2_P$J24") (pintype "bidirectional"))
    )
    (net (code "11") (name "D+{slash}1.5D") (class "Default")
      (node (ref "D1") (pin "4") (pinfunction "I/O2_2_4") (pintype "bidirectional"))
    )
    (net (code "12") (name "D+{slash}2.7D") (class "Default")
      (node (ref "U1") (pin "P$AD6") (pinfunction "D+_P$AD6") (pintype "bidirectional"))
    )
    (net (code "13") (name "D-{slash}1.5D") (class "Default")
      (node (ref "D1") (pin "6") (pinfunction "I/O1_2_6") (pintype "bidirectional"))
    )
    (net (code "14") (name "D-{slash}2.7D") (class "Default")
      (node (ref "U1") (pin "P$AD4") (pinfunction "D-_P$AD4") (pintype "bidirectional"))
    )
    (net (code "15") (name "DN") (class "Default")
      (node (ref "D1") (pin "1") (pinfunction "I/O1_1_1") (pintype "bidirectional"))
      (node (ref "J4") (pin "A7") (pinfunction "DN1_A7") (pintype "bidirectional"))
      (node (ref "J4") (pin "B7") (pinfunction "DN2_B7") (pintype "bidirectional"))
    )
    (net (code "16") (name "DP") (class "Default")
      (node (ref "D1") (pin "3") (pinfunction "I/O2_1_3") (pintype "bidirectional"))
      (node (ref "J4") (pin "A6") (pinfunction "DP1_A6") (pintype "bidirectional"))
      (node (ref "J4") (pin "B6") (pinfunction "DP2_B6") (pintype "bidirectional"))
    )
    (net (code "17") (name "EPD_3V3") (class "Default")
      (node (ref "C1-EP-DR") (pin "1") (pinfunction "1_1") (pintype "passive"))
      (node (ref "DMG2305UX-7") (pin "3") (pinfunction "D_3") (pintype "bidirectional"))
      (node (ref "EPD_C5") (pin "2") (pinfunction "2_2") (pintype "passive"))
      (node (ref "J1") (pin "15") (pinfunction "15_15") (pintype "bidirectional"))
      (node (ref "J1") (pin "16") (pinfunction "16_16") (pintype "bidirectional"))
      (node (ref "L5") (pin "2") (pinfunction "2_2") (pintype "passive"))
    )
    (net (code "18") (name "EPD_BUSY{slash}1.5D") (class "Default")
      (node (ref "J1") (pin "9") (pinfunction "9_9") (pintype "bidirectional"))
    )
    (net (code "19") (name "EPD_BUSY{slash}2.2D") (class "Default")
      (node (ref "U1") (pin "P$AD12") (pinfunction "P0.17_P$AD12") (pintype "bidirectional"))
    )
    (net (code "20") (name "EPD_CS{slash}1.4C") (class "Default")
      (node (ref "J1") (pin "12") (pinfunction "12_12") (pintype "bidirectional"))
    )
    (net (code "21") (name "EPD_CS{slash}2.2D") (class "Default")
      (node (ref "U1") (pin "P$K2") (pinfunction "P0.05/AIN3_P$K2") (pintype "bidirectional"))
    )
    (net (code "22") (name "EPD_DC{slash}1.5D") (class "Default")
      (node (ref "J1") (pin "11") (pinfunction "11_11") (pintype "bidirectional"))
    )
    (net (code "23") (name "EPD_DC{slash}2.2D") (class "Default")
      (node (ref "U1") (pin "P$AD10") (pinfunction "P0.15_P$AD10") (pintype "bidirectional"))
    )
    (net (code "24") (name "EPD_RST{slash}1.5D") (class "Default")
      (node (ref "J1") (pin "10") (pinfunction "10_10") (pintype "bidirectional"))
    )
    (net (code "25") (name "EPD_RST{slash}2.2D") (class "Default")
      (node (ref "U1") (pin "P$AC11") (pinfunction "P0.16_P$AC11") (pintype "bidirectional"))
    )
    (net (code "26") (name "GDR") (class "Default")
      (node (ref "J1") (pin "2") (pinfunction "2_2") (pintype "bidirectional"))
    )
    (net (code "27") (name "GND") (class "Default")
      (node (ref "C1") (pin "2") (pinfunction "2_2") (pintype "passive"))
      (node (ref "C1-EP-DR") (pin "2") (pinfunction "2_2") (pintype "passive"))
      (node (ref "C10") (pin "2") (pinfunction "2_2") (pintype "passive"))
      (node (ref "C11") (pin "2") (pinfunction "2_2") (pintype "passive"))
      (node (ref "C12") (pin "2") (pinfunction "2_2") (pintype "passive"))
      (node (ref "C13") (pin "2") (pinfunction "2_2") (pintype "passive"))
      (node (ref "C14") (pin "2") (pinfunction "2_2") (pintype "passive"))
      (node (ref "C15") (pin "2") (pinfunction "2_2") (pintype "passive"))
      (node (ref "C16") (pin "2") (pinfunction "2_2") (pintype "passive"))
      (node (ref "C17") (pin "1") (pinfunction "1_1") (pintype "passive"))
      (node (ref "C18") (pin "1") (pinfunction "1_1") (pintype "passive"))
      (node (ref "C19") (pin "2") (pinfunction "2_2") (pintype "passive"))
      (node (ref "C2") (pin "2") (pinfunction "2_2") (pintype "passive"))
      (node (ref "C20") (pin "2") (pinfunction "2_2") (pintype "passive"))
      (node (ref "C21") (pin "2") (pinfunction "2_2") (pintype "passive"))
      (node (ref "C22") (pin "2") (pinfunction "2_2") (pintype "passive"))
      (node (ref "C23") (pin "2") (pinfunction "2_2") (pintype "passive"))
      (node (ref "C24") (pin "1") (pinfunction "1_1") (pintype "passive"))
      (node (ref "C25") (pin "2") (pinfunction "2_2") (pintype "passive"))
      (node (ref "C27") (pin "1") (pinfunction "1_1") (pintype "passive"))
      (node (ref "C29") (pin "1") (pinfunction "1_1") (pintype "passive"))
      (node (ref "C3") (pin "2") (pinfunction "2_2") (pintype "passive"))
      (node (ref "C30") (pin "1") (pinfunction "1_1") (pintype "passive"))
      (node (ref "C31") (pin "1") (pinfunction "1_1") (pintype "passive"))
      (node (ref "C32") (pin "1") (pinfunction "1_1") (pintype "passive"))
      (node (ref "C33") (pin "2") (pinfunction "2_2") (pintype "passive"))
      (node (ref "C34") (pin "1") (pinfunction "1_1") (pintype "passive"))
      (node (ref "C37") (pin "1") (pinfunction "1_1") (pintype "passive"))
      (node (ref "C38") (pin "2") (pinfunction "2_2") (pintype "passive"))
      (node (ref "C39") (pin "2") (pinfunction "2_2") (pintype "passive"))
      (node (ref "C4") (pin "2") (pinfunction "2_2") (pintype "passive"))
      (node (ref "C42") (pin "2") (pinfunction "2_2") (pintype "passive"))
      (node (ref "C43") (pin "2") (pinfunction "2_2") (pintype "passive"))
      (node (ref "C5") (pin "2") (pinfunction "2_2") (pintype "passive"))
      (node (ref "C6") (pin "2") (pinfunction "2_2") (pintype "passive"))
      (node (ref "C7") (pin "2") (pinfunction "2_2") (pintype "passive"))
      (node (ref "C8") (pin "2") (pinfunction "2_2") (pintype "passive"))
      (node (ref "C9") (pin "2") (pinfunction "2_2") (pintype "passive"))
      (node (ref "D1") (pin "2") (pinfunction "GND_2") (pintype "bidirectional"))
      (node (ref "D4") (pin "1") (pinfunction "K_1") (pintype "bidirectional"))
      (node (ref "EPD_C1") (pin "1") (pinfunction "1_1") (pintype "passive"))
      (node (ref "EPD_C10") (pin "1") (pinfunction "1_1") (pintype "passive"))
      (node (ref "EPD_C11") (pin "1") (pinfunction "1_1") (pintype "passive"))
      (node (ref "EPD_C12") (pin "1") (pinfunction "1_1") (pintype "passive"))
      (node (ref "EPD_C2") (pin "1") (pinfunction "1_1") (pintype "passive"))
      (node (ref "EPD_C5") (pin "1") (pinfunction "1_1") (pintype "passive"))
      (node (ref "EPD_C6") (pin "1") (pinfunction "1_1") (pintype "passive"))
      (node (ref "EPD_C7") (pin "1") (pinfunction "1_1") (pintype "passive"))
      (node (ref "EPD_C8") (pin "1") (pinfunction "1_1") (pintype "passive"))
      (node (ref "EPD_C9") (pin "1") (pinfunction "1_1") (pintype "passive"))
      (node (ref "IC1") (pin "D2") (pinfunction "GND_D2") (pintype "bidirectional"))
      (node (ref "IC2") (pin "B1") (pinfunction "IN/TRIG_B1") (pintype "bidirectional"))
      (node (ref "IC2") (pin "B3") (pinfunction "GND_B3") (pintype "bidirectional"))
      (node (ref "IC3") (pin "8") (pinfunction "GNDIO_8") (pintype "bidirectional"))
      (node (ref "IC3") (pin "9") (pinfunction "GND_9") (pintype "bidirectional"))
      (node (ref "IC9") (pin "B1") (pinfunction "VSEL_B1") (pintype "bidirectional"))
      (node (ref "IC9") (pin "C1") (pinfunction "AGND_C1") (pintype "bidirectional"))
      (node (ref "IC9") (pin "C2") (pinfunction "PGND_1_C2") (pintype "bidirectional"))
      (node (ref "IC9") (pin "C3") (pinfunction "PGND_2_C3") (pintype "bidirectional"))
      (node (ref "J1") (pin "17") (pinfunction "17_17") (pintype "bidirectional"))
      (node (ref "J1") (pin "8") (pinfunction "8_8") (pintype "bidirectional"))
      (node (ref "J1") (pin "MP1") (pinfunction "MP1_MP1") (pintype "bidirectional"))
      (node (ref "J1") (pin "MP2") (pinfunction "MP2_MP2") (pintype "bidirectional"))
      (node (ref "J2") (pin "3") (pinfunction "3_3") (pintype "bidirectional"))
      (node (ref "J2") (pin "5") (pinfunction "5_5") (pintype "bidirectional"))
      (node (ref "J4") (pin "A12_B1") (pinfunction "GND_A12_B1") (pintype "power_in"))
      (node (ref "J4") (pin "A1_B12") (pinfunction "GND_A1_B12") (pintype "power_in"))
      (node (ref "J4") (pin "SH1") (pinfunction "SHIELD_SH1") (pintype "passive"))
      (node (ref "J4") (pin "SH2") (pinfunction "SHIELD_SH2") (pintype "passive"))
      (node (ref "J4") (pin "SH3") (pinfunction "SHIELD_SH3") (pintype "passive"))
      (node (ref "J4") (pin "SH4") (pinfunction "SHIELD_SH4") (pintype "passive"))
      (node (ref "R1_USB") (pin "1") (pinfunction "1_1") (pintype "bidirectional"))
      (node (ref "R2_EP_DR") (pin "1") (pinfunction "1_1") (pintype "bidirectional"))
      (node (ref "R2_USB") (pin "2") (pinfunction "2_2") (pintype "bidirectional"))
      (node (ref "R3") (pin "1") (pinfunction "1_1") (pintype "bidirectional"))
      (node (ref "R9") (pin "1") (pinfunction "1_1") (pintype "bidirectional"))
      (node (ref "R_TYPE_SEL") (pin "1") (pinfunction "1_1") (pintype "bidirectional"))
      (node (ref "SJ1") (pin "1") (pinfunction "1_1") (pintype "passive"))
      (node (ref "SW_DN") (pin "1") (pinfunction "1_1") (pintype "passive"))
      (node (ref "SW_ENT") (pin "1") (pinfunction "1_1") (pintype "passive"))
      (node (ref "SW_UP") (pin "1") (pinfunction "1_1") (pintype "passive"))
      (node (ref "TP2") (pin "TP") (pinfunction "TP_TP") (pintype "input"))
      (node (ref "TP_GND") (pin "TP") (pinfunction "TP_TP") (pintype "input"))
      (node (ref "U1") (pin "P$74") (pinfunction "VSS_PAD_P$74") (pintype "bidirectional"))
      (node (ref "U1") (pin "P$75") (pinfunction "VSS_PAD_P$75") (pintype "bidirectional"))
      (node (ref "U1") (pin "P$76") (pinfunction "VSS_PAD_P$76") (pintype "bidirectional"))
      (node (ref "U1") (pin "P$77") (pinfunction "VSS_PAD_P$77") (pintype "bidirectional"))
      (node (ref "U1") (pin "P$78") (pinfunction "VSS_PAD_P$78") (pintype "bidirectional"))
      (node (ref "U1") (pin "P$79") (pinfunction "VSS_PAD_P$79") (pintype "bidirectional"))
      (node (ref "U1") (pin "P$80") (pinfunction "VSS_PAD_P$80") (pintype "bidirectional"))
      (node (ref "U1") (pin "P$81") (pinfunction "VSS_PAD_P$81") (pintype "bidirectional"))
      (node (ref "U1") (pin "P$82") (pinfunction "VSS_PAD_P$82") (pintype "bidirectional"))
      (node (ref "U1") (pin "P$83") (pinfunction "VSS_PAD_P$83") (pintype "bidirectional"))
      (node (ref "U1") (pin "P$84") (pinfunction "VSS_PAD_P$84") (pintype "bidirectional"))
      (node (ref "U1") (pin "P$85") (pinfunction "VSS_PAD_P$85") (pintype "bidirectional"))
      (node (ref "U1") (pin "P$86") (pinfunction "VSS_PAD_P$86") (pintype "bidirectional"))
      (node (ref "U1") (pin "P$87") (pinfunction "VSS_PAD_P$87") (pintype "bidirectional"))
      (node (ref "U1") (pin "P$88") (pinfunction "VSS_PAD_P$88") (pintype "bidirectional"))
      (node (ref "U1") (pin "P$89") (pinfunction "VSS_PAD_P$89") (pintype "bidirectional"))
      (node (ref "U1") (pin "P$90") (pinfunction "VSS_PAD_P$90") (pintype "bidirectional"))
      (node (ref "U1") (pin "P$B7") (pinfunction "VSS_P$B7") (pintype "power_in"))
      (node (ref "U1") (pin "P$F23") (pinfunction "VSS_PA_P$F23") (pintype "bidirectional"))
      (node (ref "U3") (pin "1") (pinfunction "CTG_1") (pintype "power_in"))
      (node (ref "U3") (pin "4") (pinfunction "GND_4") (pintype "power_in"))
      (node (ref "U3") (pin "6") (pinfunction "QSTRT_6") (pintype "input"))
      (node (ref "U3") (pin "9") (pinfunction "EP_9") (pintype "power_in"))
      (node (ref "X1") (pin "2") (pinfunction "2_2") (pintype "passive"))
      (node (ref "X1") (pin "4") (pinfunction "4_4") (pintype "passive"))
    )
    (net (code "28") (name "HAPTIC_EN{slash}1.4C") (class "Default")
      (node (ref "IC2") (pin "A1") (pinfunction "EN_A1") (pintype "bidirectional"))
    )
    (net (code "29") (name "HAPTIC_EN{slash}2.6A") (class "Default")
      (node (ref "U1") (pin "P$U1") (pinfunction "P0.12_P$U1") (pintype "bidirectional"))
    )
    (net (code "30") (name "IMU_INT1") (class "Default")
      (node (ref "IC3") (pin "5") (pinfunction "INT1_5") (pintype "bidirectional"))
      (node (ref "U1") (pin "P$N1") (pinfunction "P0.08_P$N1") (pintype "bidirectional"))
    )
    (net (code "31") (name "IMU_INT2") (class "Default")
      (node (ref "IC3") (pin "6") (pinfunction "INT2_6") (pintype "bidirectional"))
      (node (ref "U1") (pin "P$P2") (pinfunction "P1.08_P$P2") (pintype "bidirectional"))
    )
    (net (code "32") (name "LX1") (class "Default")
      (node (ref "IC9") (pin "B2") (pinfunction "SW1_1_B2") (pintype "bidirectional"))
      (node (ref "IC9") (pin "B3") (pinfunction "SW1_2_B3") (pintype "bidirectional"))
      (node (ref "L7") (pin "1") (pinfunction "1_1") (pintype "bidirectional"))
    )
    (net (code "33") (name "LX2") (class "Default")
      (node (ref "IC9") (pin "D2") (pinfunction "SW2_1_D2") (pintype "bidirectional"))
      (node (ref "IC9") (pin "D3") (pinfunction "SW2_2_D3") (pintype "bidirectional"))
      (node (ref "L7") (pin "2") (pinfunction "2_2") (pintype "bidirectional"))
    )
    (net (code "34") (name "MOSI{slash}1.5B") (class "Default")
      (node (ref "J1") (pin "14") (pinfunction "14_14") (pintype "bidirectional"))
    )
    (net (code "35") (name "MOSI{slash}2.2D") (class "Default")
      (node (ref "U1") (pin "P$B13") (pinfunction "P0.03/AIN1_P$B13") (pintype "bidirectional"))
    )
    (net (code "36") (name "N$3") (class "Default")
      (node (ref "Q3") (pin "1") (pinfunction "G_1") (pintype "bidirectional"))
      (node (ref "R2_EP_DR") (pin "2") (pinfunction "2_2") (pintype "bidirectional"))
    )
    (net (code "37") (name "N$5") (class "Default")
      (node (ref "C42") (pin "1") (pinfunction "1_1") (pintype "passive"))
      (node (ref "C43") (pin "1") (pinfunction "1_1") (pintype "passive"))
    )
    (net (code "38") (name "Net-(D2-K)") (class "Default")
      (node (ref "C2-EP-DR") (pin "1") (pinfunction "1_1") (pintype "passive"))
      (node (ref "D2") (pin "1") (pinfunction "K_1") (pintype "bidirectional"))
      (node (ref "D4") (pin "2") (pinfunction "A_2") (pintype "bidirectional"))
    )
    (net (code "39") (name "Net-(D5-A)") (class "Default")
      (node (ref "C2-EP-DR") (pin "2") (pinfunction "2_2") (pintype "passive"))
      (node (ref "D5") (pin "2") (pinfunction "A_2") (pintype "bidirectional"))
      (node (ref "L5") (pin "1") (pinfunction "1_1") (pintype "passive"))
      (node (ref "Q3") (pin "3") (pinfunction "D_3") (pintype "bidirectional"))
    )
    (net (code "40") (name "Net-(EPD_C1-Pad2)") (class "Default")
      (node (ref "EPD_C1") (pin "2") (pinfunction "2_2") (pintype "passive"))
      (node (ref "J1") (pin "5") (pinfunction "5_5") (pintype "bidirectional"))
    )
    (net (code "41") (name "Net-(EPD_C2-Pad2)") (class "Default")
      (node (ref "EPD_C2") (pin "2") (pinfunction "2_2") (pintype "passive"))
      (node (ref "J1") (pin "4") (pinfunction "4_4") (pintype "bidirectional"))
    )
    (net (code "42") (name "Net-(EPD_C6-Pad2)") (class "Default")
      (node (ref "EPD_C6") (pin "2") (pinfunction "2_2") (pintype "passive"))
      (node (ref "J1") (pin "18") (pinfunction "18_18") (pintype "bidirectional"))
    )
    (net (code "43") (name "Net-(EPD_C7-Pad2)") (class "Default")
      (node (ref "EPD_C7") (pin "2") (pinfunction "2_2") (pintype "passive"))
      (node (ref "J1") (pin "19") (pinfunction "19_19") (pintype "bidirectional"))
    )
    (net (code "44") (name "Net-(EPD_C8-Pad2)") (class "Default")
      (node (ref "EPD_C8") (pin "2") (pinfunction "2_2") (pintype "passive"))
      (node (ref "J1") (pin "20") (pinfunction "20_20") (pintype "bidirectional"))
    )
    (net (code "45") (name "Net-(EPD_C10-Pad2)") (class "Default")
      (node (ref "EPD_C10") (pin "2") (pinfunction "2_2") (pintype "passive"))
      (node (ref "J1") (pin "22") (pinfunction "22_22") (pintype "bidirectional"))
    )
    (net (code "46") (name "Net-(EPD_C12-Pad2)") (class "Default")
      (node (ref "EPD_C12") (pin "2") (pinfunction "2_2") (pintype "passive"))
      (node (ref "J1") (pin "24") (pinfunction "24_24") (pintype "bidirectional"))
    )
    (net (code "47") (name "Net-(IC1-TS{slash}MR)") (class "Default")
      (node (ref "IC1") (pin "D1") (pinfunction "TS/MR_D1") (pintype "bidirectional"))
      (node (ref "R9") (pin "2") (pinfunction "2_2") (pintype "bidirectional"))
    )
    (net (code "48") (name "Net-(IC2-REG)") (class "Default")
      (node (ref "C32") (pin "2") (pinfunction "2_2") (pintype "passive"))
      (node (ref "IC2") (pin "A2") (pinfunction "REG_A2") (pintype "bidirectional"))
    )
    (net (code "49") (name "Net-(IC3-SDO)") (class "Default")
      (node (ref "IC3") (pin "1") (pinfunction "SDO_1") (pintype "bidirectional"))
      (node (ref "R3") (pin "2") (pinfunction "2_2") (pintype "bidirectional"))
    )
    (net (code "50") (name "Net-(IC9-SCL)") (class "Default")
      (node (ref "IC9") (pin "D1") (pinfunction "SCL_D1") (pintype "bidirectional"))
      (node (ref "R4") (pin "2") (pinfunction "2_2") (pintype "bidirectional"))
    )
    (net (code "51") (name "Net-(IC9-SDA)") (class "Default")
      (node (ref "IC9") (pin "E1") (pinfunction "SDA_E1") (pintype "bidirectional"))
      (node (ref "R2") (pin "2") (pinfunction "2_2") (pintype "bidirectional"))
    )
    (net (code "52") (name "Net-(J4-CC1)") (class "Default")
      (node (ref "J4") (pin "A5") (pinfunction "CC1_A5") (pintype "bidirectional"))
      (node (ref "R1_USB") (pin "2") (pinfunction "2_2") (pintype "bidirectional"))
    )
    (net (code "53") (name "Net-(J4-CC2)") (class "Default")
      (node (ref "J4") (pin "B5") (pinfunction "CC2_B5") (pintype "bidirectional"))
      (node (ref "R2_USB") (pin "1") (pinfunction "1_1") (pintype "bidirectional"))
    )
    (net (code "54") (name "Net-(L2-Pad2)") (class "Default")
      (node (ref "L2") (pin "2") (pinfunction "2_2") (pintype "passive"))
      (node (ref "L3") (pin "1") (pinfunction "1_1") (pintype "passive"))
    )
    (net (code "55") (name "Net-(R1_EP_DR-Pad1)") (class "Default")
      (node (ref "R1_EP_DR") (pin "1") (pinfunction "1_1") (pintype "bidirectional"))
      (node (ref "R_TYPE_SEL") (pin "2") (pinfunction "2_2") (pintype "bidirectional"))
      (node (ref "SJ1") (pin "2") (pinfunction "2_2") (pintype "passive"))
    )
    (net (code "56") (name "Net-(U1-ANT)") (class "Default")
      (node (ref "C3") (pin "1") (pinfunction "1_1") (pintype "passive"))
      (node (ref "L1") (pin "1") (pinfunction "1_1") (pintype "passive"))
      (node (ref "U1") (pin "P$H23") (pinfunction "ANT_P$H23") (pintype "bidirectional"))
    )
    (net (code "57") (name "Net-(U1-DCC)") (class "Default")
      (node (ref "L2") (pin "1") (pinfunction "1_1") (pintype "passive"))
      (node (ref "U1") (pin "P$B3") (pinfunction "DCC_P$B3") (pintype "output"))
    )
    (net (code "58") (name "Net-(U1-DEC2)") (class "Default")
      (node (ref "C13") (pin "1") (pinfunction "1_1") (pintype "passive"))
      (node (ref "U1") (pin "P$A18") (pinfunction "DEC2_P$A18") (pintype "bidirectional"))
    )
    (net (code "59") (name "Net-(U1-DEC3V3)") (class "Default")
      (node (ref "C20") (pin "1") (pinfunction "1_1") (pintype "passive"))
      (node (ref "U1") (pin "P$AC5") (pinfunction "DEC3V3_P$AC5") (pintype "bidirectional"))
    )
    (net (code "60") (name "Net-(U1-DEC5)") (class "Default")
      (node (ref "C9") (pin "1") (pinfunction "1_1") (pintype "passive"))
      (node (ref "U1") (pin "P$N24") (pinfunction "DEC5_P$N24") (pintype "bidirectional"))
    )
    (net (code "61") (name "Net-(U1-XC1)") (class "Default")
      (node (ref "C1") (pin "1") (pinfunction "1_1") (pintype "passive"))
      (node (ref "U1") (pin "P$B24") (pinfunction "XC1_P$B24") (pintype "input"))
      (node (ref "X1") (pin "1") (pinfunction "1_1") (pintype "passive"))
    )
    (net (code "62") (name "Net-(U1-XC2)") (class "Default")
      (node (ref "C2") (pin "1") (pinfunction "1_1") (pintype "passive"))
      (node (ref "U1") (pin "P$A23") (pinfunction "XC2_P$A23") (pintype "output"))
      (node (ref "X1") (pin "3") (pinfunction "3_3") (pintype "passive"))
    )
    (net (code "63") (name "OUT+") (class "Default")
      (node (ref "IC2") (pin "A3") (pinfunction "OUT+_A3") (pintype "bidirectional"))
      (node (ref "TP_OP") (pin "TP") (pinfunction "TP_TP") (pintype "input"))
    )
    (net (code "64") (name "OUT-") (class "Default")
      (node (ref "IC2") (pin "C3") (pinfunction "OUT-_C3") (pintype "bidirectional"))
      (node (ref "TP_ON") (pin "TP") (pinfunction "TP_TP") (pintype "input"))
    )
    (net (code "65") (name "P0.04") (class "Default")
      (node (ref "U1") (pin "P$J1") (pinfunction "P0.04/AIN2_P$J1") (pintype "bidirectional"))
    )
    (net (code "66") (name "P0.13{slash}1.5D") (class "Default")
      (node (ref "C30") (pin "2") (pinfunction "2_2") (pintype "passive"))
      (node (ref "R5") (pin "1") (pinfunction "1_1") (pintype "bidirectional"))
      (node (ref "SW_UP") (pin "2") (pinfunction "2_2") (pintype "passive"))
    )
    (net (code "67") (name "P0.13{slash}2.6C") (class "Default")
      (node (ref "U1") (pin "P$AD8") (pinfunction "P0.13_P$AD8") (pintype "bidirectional"))
    )
    (net (code "68") (name "P0.14{slash}1.5D") (class "Default")
      (node (ref "C31") (pin "2") (pinfunction "2_2") (pintype "passive"))
      (node (ref "R8") (pin "1") (pinfunction "1_1") (pintype "bidirectional"))
      (node (ref "SW_ENT") (pin "2") (pinfunction "2_2") (pintype "passive"))
    )
    (net (code "69") (name "P0.14{slash}2.7C") (class "Default")
      (node (ref "U1") (pin "P$AC9") (pinfunction "P0.14_P$AC9") (pintype "bidirectional"))
    )
    (net (code "70") (name "P0.19") (class "Default")
      (node (ref "U1") (pin "P$AC15") (pinfunction "P0.19_P$AC15") (pintype "bidirectional"))
    )
    (net (code "71") (name "P0.20") (class "Default")
      (node (ref "U1") (pin "P$AD16") (pinfunction "P0.20_P$AD16") (pintype "bidirectional"))
    )
    (net (code "72") (name "P0.21") (class "Default")
      (node (ref "U1") (pin "P$AC17") (pinfunction "P0.21_P$AC17") (pintype "bidirectional"))
    )
    (net (code "73") (name "P0.22") (class "Default")
      (node (ref "U1") (pin "P$AD18") (pinfunction "P0.22_P$AD18") (pintype "bidirectional"))
    )
    (net (code "74") (name "P0.23") (class "Default")
      (node (ref "U1") (pin "P$AC19") (pinfunction "P0.23_P$AC19") (pintype "bidirectional"))
    )
    (net (code "75") (name "P0.24") (class "Default")
      (node (ref "U1") (pin "P$AD20") (pinfunction "P0.24_P$AD20") (pintype "bidirectional"))
    )
    (net (code "76") (name "P0.25") (class "Default")
      (node (ref "U1") (pin "P$AC21") (pinfunction "P0.25_P$AC21") (pintype "bidirectional"))
    )
    (net (code "77") (name "P0.26") (class "Default")
      (node (ref "U1") (pin "P$G1") (pinfunction "P0.26_P$G1") (pintype "bidirectional"))
    )
    (net (code "78") (name "P0.27") (class "Default")
      (node (ref "U1") (pin "P$H2") (pinfunction "P0.27_P$H2") (pintype "bidirectional"))
    )
    (net (code "79") (name "P0.28") (class "Default")
      (node (ref "U1") (pin "P$B11") (pinfunction "P0.28/AIN4_P$B11") (pintype "bidirectional"))
    )
    (net (code "80") (name "P0.29") (class "Default")
      (node (ref "U1") (pin "P$A10") (pinfunction "P0.29/AIN5_P$A10") (pintype "bidirectional"))
    )
    (net (code "81") (name "P0.30") (class "Default")
      (node (ref "U1") (pin "P$B9") (pinfunction "P0.30/AIN6_P$B9") (pintype "bidirectional"))
    )
    (net (code "82") (name "P0.31") (class "Default")
      (node (ref "U1") (pin "P$A8") (pinfunction "P0.31/AIN7_P$A8") (pintype "bidirectional"))
    )
    (net (code "83") (name "P1.01{slash}1.6C") (class "Default")
      (node (ref "DMG2305UX-7") (pin "1") (pinfunction "G_1") (pintype "bidirectional"))
      (node (ref "R_PWR_EPD") (pin "1") (pinfunction "1_1") (pintype "passive"))
    )
    (net (code "84") (name "P1.01{slash}2.4B") (class "Default")
      (node (ref "U1") (pin "P$Y23") (pinfunction "P1.01_P$Y23") (pintype "bidirectional"))
    )
    (net (code "85") (name "P1.02{slash}1.6C") (class "Default")
      (node (ref "C29") (pin "2") (pinfunction "2_2") (pintype "passive"))
      (node (ref "R7") (pin "1") (pinfunction "1_1") (pintype "bidirectional"))
      (node (ref "SW_DN") (pin "2") (pinfunction "2_2") (pintype "passive"))
    )
    (net (code "86") (name "P1.02{slash}2.8C") (class "Default")
      (node (ref "U1") (pin "P$W24") (pinfunction "P1.02_P$W24") (pintype "bidirectional"))
    )
    (net (code "87") (name "P1.03") (class "Default")
      (node (ref "U1") (pin "P$V23") (pinfunction "P1.03_P$V23") (pintype "bidirectional"))
    )
    (net (code "88") (name "P1.04") (class "Default")
      (node (ref "U1") (pin "P$U24") (pinfunction "P1.04_P$U24") (pintype "bidirectional"))
    )
    (net (code "89") (name "P1.05") (class "Default")
      (node (ref "U1") (pin "P$T23") (pinfunction "P1.05_P$T23") (pintype "bidirectional"))
    )
    (net (code "90") (name "P1.06") (class "Default")
      (node (ref "U1") (pin "P$R24") (pinfunction "P1.06_P$R24") (pintype "bidirectional"))
    )
    (net (code "91") (name "P1.07") (class "Default")
      (node (ref "U1") (pin "P$P23") (pinfunction "P1.07_P$P23") (pintype "bidirectional"))
    )
    (net (code "92") (name "P1.09") (class "Default")
      (node (ref "U1") (pin "P$L24") (pinfunction "P0.09/NFC1_P$L24") (pintype "bidirectional"))
      (node (ref "U1") (pin "P$R1") (pinfunction "P1.09_P$R1") (pintype "bidirectional"))
    )
    (net (code "93") (name "P1.10") (class "Default")
      (node (ref "U1") (pin "P$A20") (pinfunction "P1.10_P$A20") (pintype "bidirectional"))
    )
    (net (code "94") (name "P1.11") (class "Default")
      (node (ref "U1") (pin "P$B19") (pinfunction "P1.11_P$B19") (pintype "bidirectional"))
    )
    (net (code "95") (name "P1.12") (class "Default")
      (node (ref "U1") (pin "P$B17") (pinfunction "P1.12_P$B17") (pintype "bidirectional"))
    )
    (net (code "96") (name "P1.13") (class "Default")
      (node (ref "U1") (pin "P$A16") (pinfunction "P1.13_P$A16") (pintype "bidirectional"))
    )
    (net (code "97") (name "P1.14") (class "Default")
      (node (ref "U1") (pin "P$B15") (pinfunction "P1.14_P$B15") (pintype "bidirectional"))
    )
    (net (code "98") (name "P1.15") (class "Default")
      (node (ref "U1") (pin "P$A14") (pinfunction "P1.15_P$A14") (pintype "bidirectional"))
    )
    (net (code "99") (name "PMIC_INT") (class "Default")
      (node (ref "IC1") (pin "A1") (pinfunction "~{INT}_A1") (pintype "bidirectional"))
      (node (ref "U1") (pin "P$T2") (pinfunction "P0.11_P$T2") (pintype "bidirectional"))
    )
    (net (code "100") (name "PREVGH") (class "Default")
      (node (ref "D5") (pin "1") (pinfunction "K_1") (pintype "bidirectional"))
      (node (ref "EPD_C9") (pin "2") (pinfunction "2_2") (pintype "passive"))
      (node (ref "J1") (pin "21") (pinfunction "21_21") (pintype "bidirectional"))
    )
    (net (code "101") (name "PREVGL") (class "Default")
      (node (ref "D2") (pin "2") (pinfunction "A_2") (pintype "bidirectional"))
      (node (ref "EPD_C11") (pin "2") (pinfunction "2_2") (pintype "passive"))
      (node (ref "J1") (pin "23") (pinfunction "23_23") (pintype "bidirectional"))
    )
    (net (code "102") (name "RESE") (class "Default")
      (node (ref "J1") (pin "3") (pinfunction "3_3") (pintype "bidirectional"))
      (node (ref "Q3") (pin "2") (pinfunction "S_2") (pintype "bidirectional"))
      (node (ref "R1_EP_DR") (pin "2") (pinfunction "2_2") (pintype "bidirectional"))
    )
    (net (code "103") (name "RESET") (class "Default")
      (node (ref "J2") (pin "6") (pinfunction "6_6") (pintype "bidirectional"))
      (node (ref "TP_RESET") (pin "TP") (pinfunction "TP_TP") (pintype "input"))
      (node (ref "U1") (pin "P$AC13") (pinfunction "P0.18/RESET_P$AC13") (pintype "bidirectional"))
    )
    (net (code "104") (name "SCK{slash}1.5B") (class "Default")
      (node (ref "J1") (pin "13") (pinfunction "13_13") (pintype "bidirectional"))
    )
    (net (code "105") (name "SCK{slash}2.2D") (class "Default")
      (node (ref "U1") (pin "P$A12") (pinfunction "P0.02/AIN0_P$A12") (pintype "bidirectional"))
    )
    (net (code "106") (name "SCL{slash}1.4C") (class "Default")
      (node (ref "IC2") (pin "C1") (pinfunction "SCL_C1") (pintype "bidirectional"))
      (node (ref "U3") (pin "7") (pinfunction "SCL_7") (pintype "input"))
    )
    (net (code "107") (name "SCL{slash}2.4C") (class "Default")
      (node (ref "IC1") (pin "B1") (pinfunction "SCL_B1") (pintype "bidirectional"))
      (node (ref "IC3") (pin "12") (pinfunction "SCX_12") (pintype "bidirectional"))
      (node (ref "R17") (pin "2") (pinfunction "2_2") (pintype "bidirectional"))
      (node (ref "R4") (pin "1") (pinfunction "1_1") (pintype "bidirectional"))
      (node (ref "TP_SCL") (pin "TP") (pinfunction "TP_TP") (pintype "input"))
      (node (ref "U1") (pin "P$M2") (pinfunction "P0.07_P$M2") (pintype "bidirectional"))
    )
    (net (code "108") (name "SDA{slash}1.4C") (class "Default")
      (node (ref "IC2") (pin "B2") (pinfunction "SDA_B2") (pintype "bidirectional"))
      (node (ref "U3") (pin "8") (pinfunction "SDA_8") (pintype "bidirectional"))
    )
    (net (code "109") (name "SDA{slash}2.4C") (class "Default")
      (node (ref "IC1") (pin "C1") (pinfunction "SDA_C1") (pintype "bidirectional"))
      (node (ref "IC3") (pin "2") (pinfunction "SDX_2") (pintype "bidirectional"))
      (node (ref "R18") (pin "2") (pinfunction "2_2") (pintype "bidirectional"))
      (node (ref "R2") (pin "1") (pinfunction "1_1") (pintype "bidirectional"))
      (node (ref "TP_SDA") (pin "TP") (pinfunction "TP_TP") (pintype "input"))
      (node (ref "U1") (pin "P$L1") (pinfunction "P0.06_P$L1") (pintype "bidirectional"))
    )
    (net (code "110") (name "SWDCLK") (class "Default")
      (node (ref "J2") (pin "4") (pinfunction "4_4") (pintype "bidirectional"))
      (node (ref "TP_SWDCLK") (pin "TP") (pinfunction "TP_TP") (pintype "input"))
      (node (ref "U1") (pin "P$AA24") (pinfunction "SWDCLK_P$AA24") (pintype "input"))
    )
    (net (code "111") (name "SWDIO") (class "Default")
      (node (ref "J2") (pin "2") (pinfunction "2_2") (pintype "bidirectional"))
      (node (ref "TP_SWDIO") (pin "TP") (pinfunction "TP_TP") (pintype "input"))
      (node (ref "U1") (pin "P$AC24") (pinfunction "SWDIO_P$AC24") (pintype "bidirectional"))
    )
    (net (code "112") (name "SWO") (class "Default")
      (node (ref "TP_SWO") (pin "TP") (pinfunction "TP_TP") (pintype "input"))
      (node (ref "U1") (pin "P$AD22") (pinfunction "P1.00_P$AD22") (pintype "bidirectional"))
    )
    (net (code "113") (name "VBAT{slash}1.2A") (class "Default")
      (node (ref "C27") (pin "2") (pinfunction "2_2") (pintype "passive"))
      (node (ref "TP1") (pin "TP") (pinfunction "TP_TP") (pintype "input"))
      (node (ref "U3") (pin "2") (pinfunction "CELL_2") (pintype "power_in"))
      (node (ref "U3") (pin "3") (pinfunction "VDD_3") (pintype "power_in"))
    )
    (net (code "114") (name "VBAT{slash}2.5C") (class "Default")
      (node (ref "C37") (pin "2") (pinfunction "2_2") (pintype "passive"))
      (node (ref "IC1") (pin "C2") (pinfunction "BAT_C2") (pintype "bidirectional"))
    )
    (net (code "115") (name "VBUS{slash}1.5D") (class "Default")
      (node (ref "D1") (pin "5") (pinfunction "VBUS_5") (pintype "bidirectional"))
      (node (ref "J4") (pin "A4_B9") (pinfunction "VBUS_A4_B9") (pintype "power_in"))
      (node (ref "J4") (pin "A9_B4") (pinfunction "VBUS_A9_B4") (pintype "power_in"))
    )
    (net (code "116") (name "VBUS{slash}2.6D") (class "Default")
      (node (ref "C21") (pin "1") (pinfunction "1_1") (pintype "passive"))
      (node (ref "C38") (pin "1") (pinfunction "1_1") (pintype "passive"))
      (node (ref "IC1") (pin "A2") (pinfunction "IN_A2") (pintype "bidirectional"))
      (node (ref "U1") (pin "P$AD2") (pinfunction "VBUS_P$AD2") (pintype "power_in"))
    )
    (net (code "117") (name "VREG") (class "Default")
      (node (ref "C23") (pin "1") (pinfunction "1_1") (pintype "passive"))
      (node (ref "C24") (pin "2") (pinfunction "2_2") (pintype "passive"))
      (node (ref "C39") (pin "1") (pinfunction "1_1") (pintype "passive"))
      (node (ref "IC1") (pin "B2") (pinfunction "SYS_B2") (pintype "bidirectional"))
      (node (ref "IC9") (pin "A1") (pinfunction "EN_A1") (pintype "bidirectional"))
      (node (ref "IC9") (pin "A2") (pinfunction "VIN_1_A2") (pintype "bidirectional"))
      (node (ref "IC9") (pin "A3") (pinfunction "VIN_2_A3") (pintype "bidirectional"))
      (node (ref "TP_VREG") (pin "TP") (pinfunction "TP_TP") (pintype "input"))
    )
    (net (code "118") (name "unconnected-(ANT1-NC-Pad2)") (class "Default")
      (node (ref "ANT1") (pin "2") (pinfunction "NC_2") (pintype "no_connect"))
    )
    (net (code "119") (name "unconnected-(IC3-ASCL-Pad11)") (class "Default")
      (node (ref "IC3") (pin "11") (pinfunction "ASCL_11") (pintype "bidirectional"))
    )
    (net (code "120") (name "unconnected-(IC3-ASDA-Pad4)") (class "Default")
      (node (ref "IC3") (pin "4") (pinfunction "ASDA_4") (pintype "bidirectional"))
    )
    (net (code "121") (name "unconnected-(J1-Pad1)") (class "Default")
      (node (ref "J1") (pin "1") (pinfunction "1_1") (pintype "bidirectional"))
    )
    (net (code "122") (name "unconnected-(J1-Pad6)") (class "Default")
      (node (ref "J1") (pin "6") (pinfunction "6_6") (pintype "bidirectional"))
    )
    (net (code "123") (name "unconnected-(J1-Pad7)") (class "Default")
      (node (ref "J1") (pin "7") (pinfunction "7_7") (pintype "bidirectional"))
    )
    (net (code "124") (name "unconnected-(J4-SBU1-PadA8)") (class "Default")
      (node (ref "J4") (pin "A8") (pinfunction "SBU1_A8") (pintype "bidirectional"))
    )
    (net (code "125") (name "unconnected-(J4-SBU2-PadB8)") (class "Default")
      (node (ref "J4") (pin "B8") (pinfunction "SBU2_B8") (pintype "bidirectional"))
    )
    (net (code "126") (name "unconnected-(U1-DCCH-PadP$AB2)") (class "Default")
      (node (ref "U1") (pin "P$AB2") (pinfunction "DCCH_P$AB2") (pintype "bidirectional"))
    )
  )
)
